# DSO_Counters.net
KiCad netlist of a schematic drawn in Altium Designer
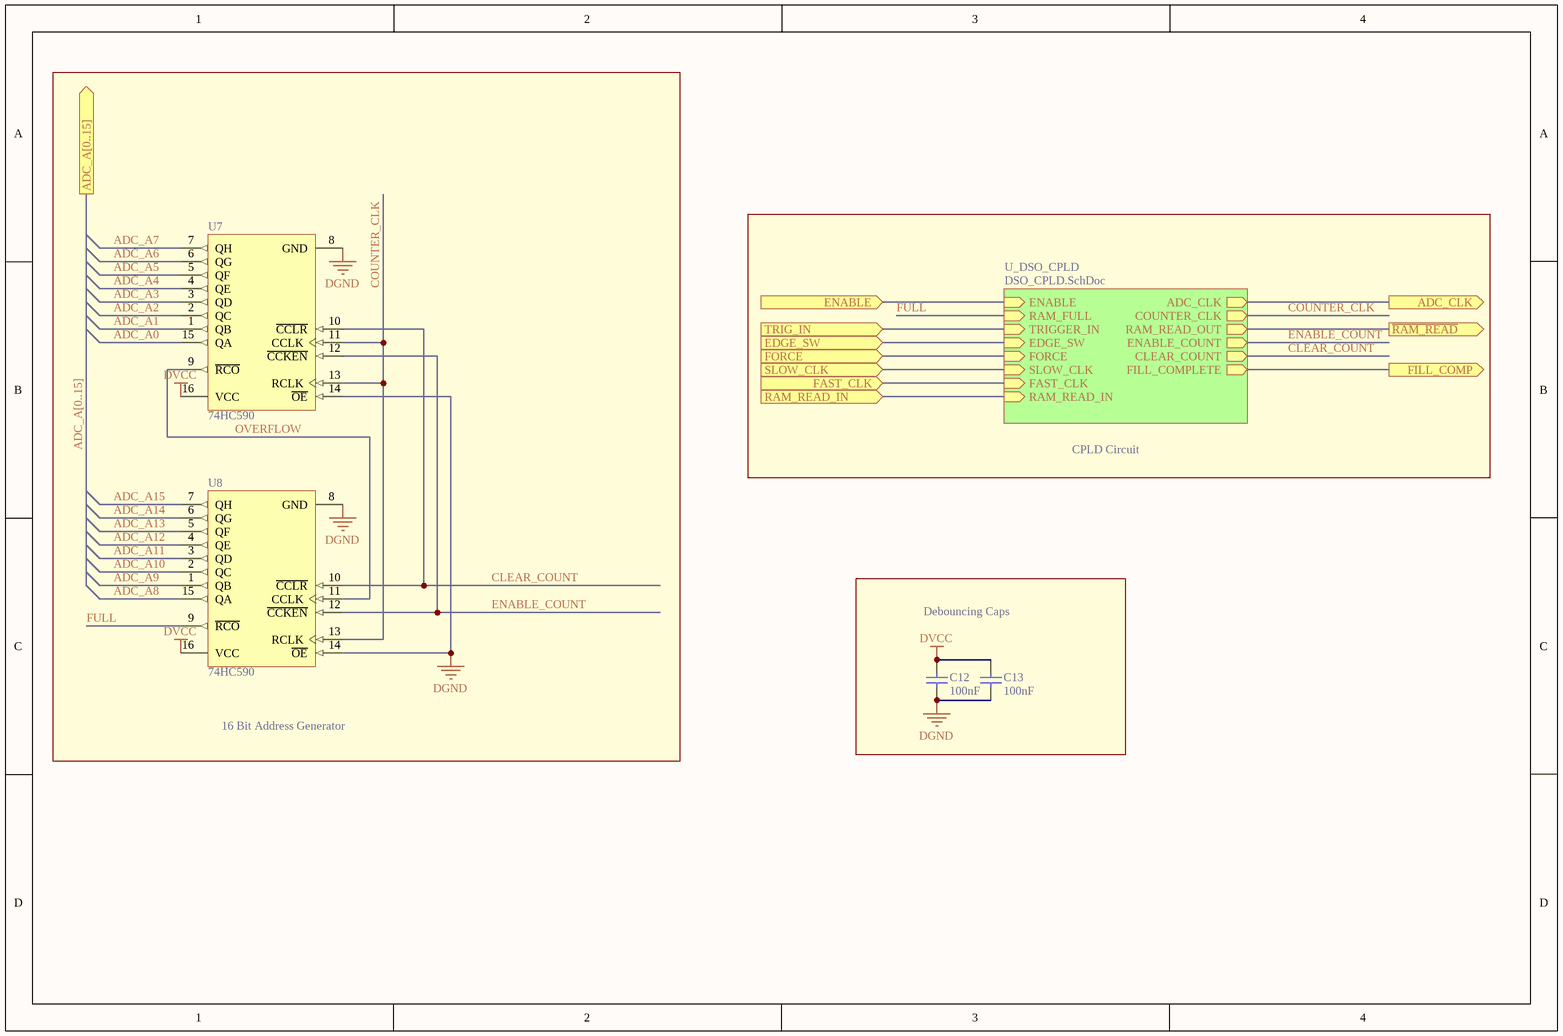
[diagram p0: DSO_Counters.SchDoc]

(export (version "E")
  (design (tool "Eeschema 10.0.6"))
  (components
    (comp (ref "C12")
      (value "100nF")
      (footprint "0805C")
      (description "Capacitor")
      (fields (field (name "REVIEWED BY") "RM - 2018/08/05"))
      (libsource (lib "DSO") (part "C"))
    )
    (comp (ref "C13")
      (value "100nF")
      (footprint "0805C")
      (description "Capacitor")
      (fields (field (name "REVIEWED BY") "RM - 2018/08/05"))
      (libsource (lib "DSO") (part "C"))
    )
    (comp (ref "U7")
      (value "74HC590")
      (footprint "SOIC-16")
      (description "8-Bit Binary Counter Register")
      (fields (field (name "REVIEWED BY") "RM - 2018/08/05"))
      (libsource (lib "DSO") (part "74HC590"))
    )
    (comp (ref "U8")
      (value "74HC590")
      (footprint "SOIC-16")
      (description "8-Bit Binary Counter Register")
      (fields (field (name "REVIEWED BY") "RM - 2018/08/05"))
      (libsource (lib "DSO") (part "74HC590"))
    )
  )
  (nets
    (net (code "1") (name "/ADC_A0") (class "Default")
      (node (ref "U7") (pin "15") (pinfunction "QA_15") (pintype "output"))
    )
    (net (code "2") (name "/ADC_A1") (class "Default")
      (node (ref "U7") (pin "1") (pinfunction "QB_1") (pintype "output"))
    )
    (net (code "3") (name "/ADC_A2") (class "Default")
      (node (ref "U7") (pin "2") (pinfunction "QC_2") (pintype "output"))
    )
    (net (code "4") (name "/ADC_A3") (class "Default")
      (node (ref "U7") (pin "3") (pinfunction "QD_3") (pintype "output"))
    )
    (net (code "5") (name "/ADC_A4") (class "Default")
      (node (ref "U7") (pin "4") (pinfunction "QE_4") (pintype "output"))
    )
    (net (code "6") (name "/ADC_A5") (class "Default")
      (node (ref "U7") (pin "5") (pinfunction "QF_5") (pintype "output"))
    )
    (net (code "7") (name "/ADC_A6") (class "Default")
      (node (ref "U7") (pin "6") (pinfunction "QG_6") (pintype "output"))
    )
    (net (code "8") (name "/ADC_A7") (class "Default")
      (node (ref "U7") (pin "7") (pinfunction "QH_7") (pintype "output"))
    )
    (net (code "9") (name "/ADC_A8") (class "Default")
      (node (ref "U8") (pin "15") (pinfunction "QA_15") (pintype "output"))
    )
    (net (code "10") (name "/ADC_A9") (class "Default")
      (node (ref "U8") (pin "1") (pinfunction "QB_1") (pintype "output"))
    )
    (net (code "11") (name "/ADC_A10") (class "Default")
      (node (ref "U8") (pin "2") (pinfunction "QC_2") (pintype "output"))
    )
    (net (code "12") (name "/ADC_A11") (class "Default")
      (node (ref "U8") (pin "3") (pinfunction "QD_3") (pintype "output"))
    )
    (net (code "13") (name "/ADC_A12") (class "Default")
      (node (ref "U8") (pin "4") (pinfunction "QE_4") (pintype "output"))
    )
    (net (code "14") (name "/ADC_A13") (class "Default")
      (node (ref "U8") (pin "5") (pinfunction "QF_5") (pintype "output"))
    )
    (net (code "15") (name "/ADC_A14") (class "Default")
      (node (ref "U8") (pin "6") (pinfunction "QG_6") (pintype "output"))
    )
    (net (code "16") (name "/ADC_A15") (class "Default")
      (node (ref "U8") (pin "7") (pinfunction "QH_7") (pintype "output"))
    )
    (net (code "19") (name "/CLEAR_COUNT") (class "Default")
      (node (ref "U7") (pin "10") (pinfunction "~{CCLR}_10") (pintype "input"))
      (node (ref "U8") (pin "10") (pinfunction "~{CCLR}_10") (pintype "input"))
    )
    (net (code "20") (name "/COUNTER_CLK") (class "Default")
      (node (ref "U7") (pin "11") (pinfunction "CCLK_11") (pintype "input"))
      (node (ref "U7") (pin "13") (pinfunction "RCLK_13") (pintype "input"))
      (node (ref "U8") (pin "13") (pinfunction "RCLK_13") (pintype "input"))
    )
    (net (code "23") (name "/ENABLE_COUNT") (class "Default")
      (node (ref "U7") (pin "12") (pinfunction "~{CCKEN}_12") (pintype "input"))
      (node (ref "U8") (pin "12") (pinfunction "~{CCKEN}_12") (pintype "input"))
    )
    (net (code "27") (name "/FULL") (class "Default")
      (node (ref "U8") (pin "9") (pinfunction "~{RCO}_9") (pintype "output"))
    )
    (net (code "28") (name "/OVERFLOW") (class "Default")
      (node (ref "U7") (pin "9") (pinfunction "~{RCO}_9") (pintype "output"))
      (node (ref "U8") (pin "11") (pinfunction "CCLK_11") (pintype "input"))
    )
    (net (code "33") (name "DGND") (class "Default")
      (node (ref "C12") (pin "2") (pinfunction "2_2") (pintype "passive"))
      (node (ref "C13") (pin "2") (pinfunction "2_2") (pintype "passive"))
      (node (ref "U7") (pin "14") (pinfunction "~{OE}_14") (pintype "input"))
      (node (ref "U7") (pin "8") (pinfunction "GND_8") (pintype "power_in"))
      (node (ref "U8") (pin "14") (pinfunction "~{OE}_14") (pintype "input"))
      (node (ref "U8") (pin "8") (pinfunction "GND_8") (pintype "power_in"))
    )
    (net (code "34") (name "DVCC") (class "Default")
      (node (ref "C12") (pin "1") (pinfunction "1_1") (pintype "passive"))
      (node (ref "C13") (pin "1") (pinfunction "1_1") (pintype "passive"))
      (node (ref "U7") (pin "16") (pinfunction "VCC_16") (pintype "power_in"))
      (node (ref "U8") (pin "16") (pinfunction "VCC_16") (pintype "power_in"))
    )
  )
)
